# iCEHAX5U1K.net
KiCad netlist of a schematic drawn in EAGLE
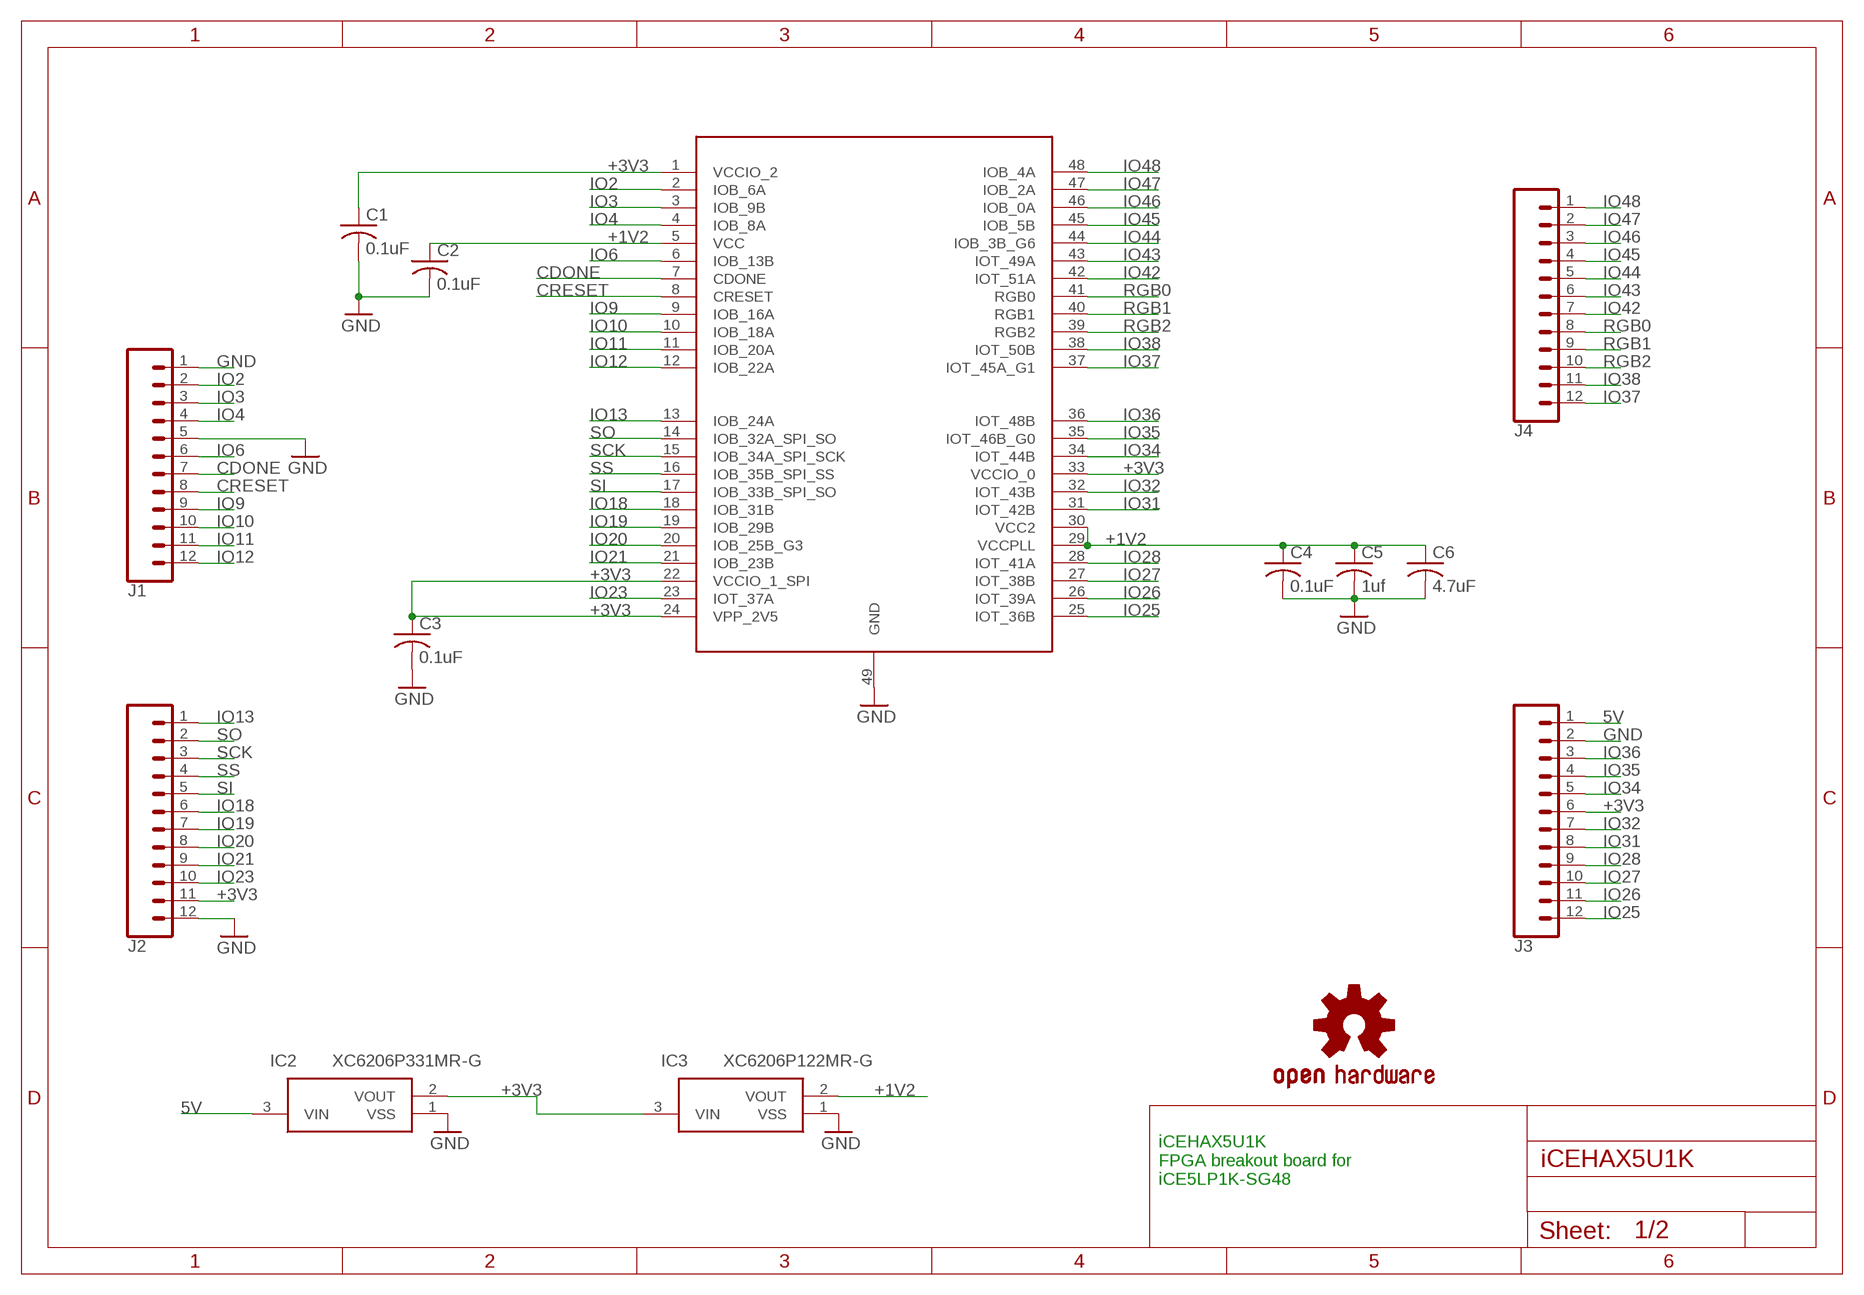
[diagram p0: schematic, sheet 1]
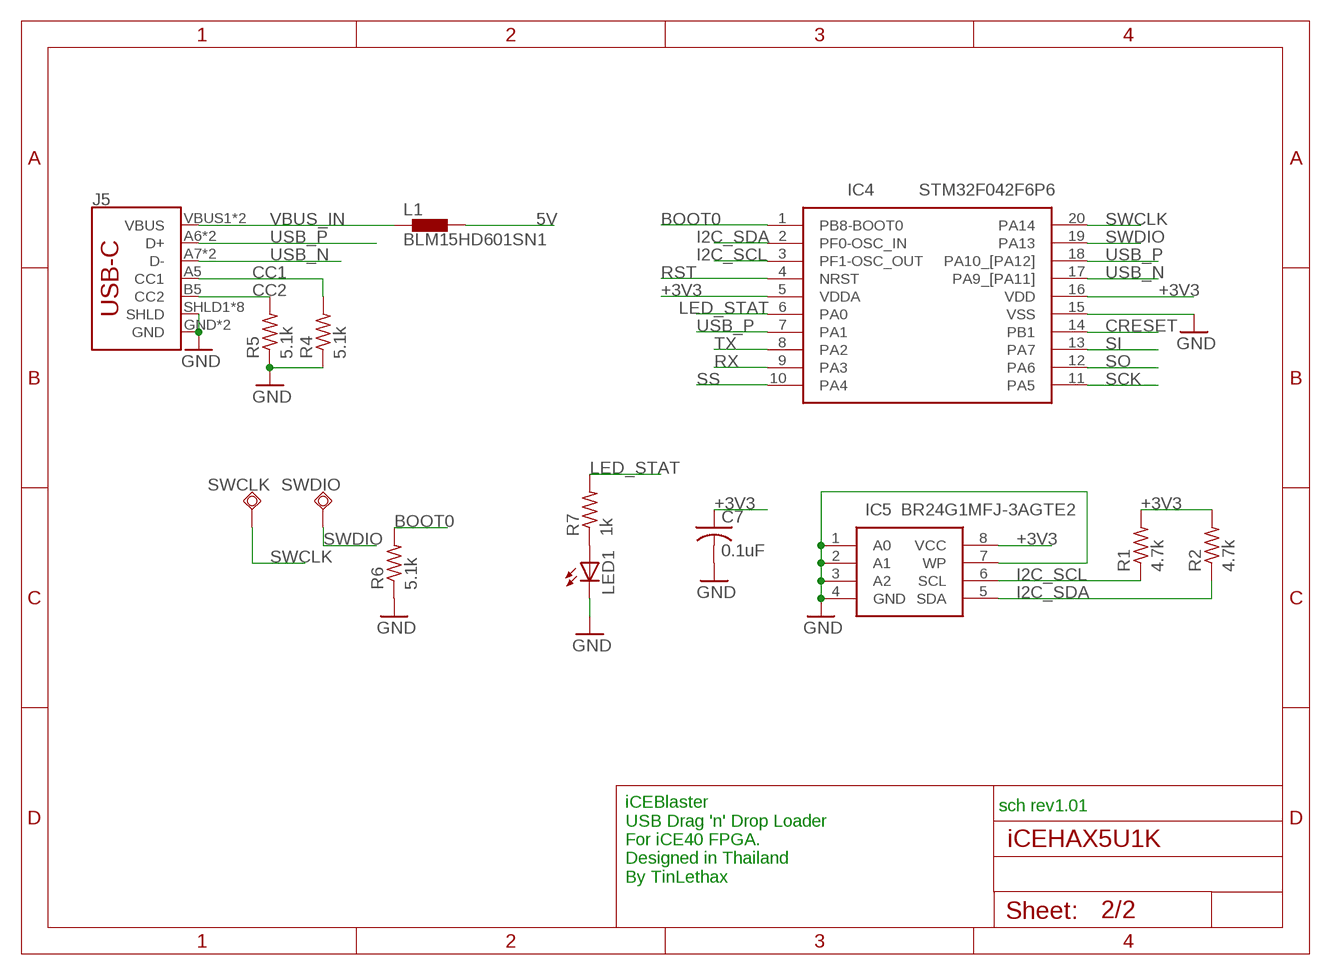
[diagram p1: schematic, sheet 2]

(export (version "E")
  (design (tool "Eeschema 10.0.6"))
  (components
    (comp (ref "C7")
      (value "0.1uF")
      (footprint "eagle-import:C0603")
      (libsource (lib "eagle-import") (part "C-USC0603"))
    )
    (comp (ref "IC4")
      (value "STM32F042F6P6")
      (footprint "eagle-import:SOP65P640X120-20N")
      (fields (field (name "MOUSER_PART_NUMBER") "511-STM32F042F6P6"))
      (libsource (lib "eagle-import") (part "STM32F042F6P6"))
    )
    (comp (ref "IC5")
      (value "BR24G1MFJ-3AGTE2")
      (footprint "eagle-import:SOP126P620X150-8N")
      (libsource (lib "eagle-import") (part "BR24G1MFJ-3AGTE2"))
    )
    (comp (ref "J5")
      (value "SPARKFUN-CONNECTORS_USB_C16PIN")
      (footprint "eagle-import:SPARKFUN-CONNECTORS_USB-C-16P")
      (libsource (lib "eagle-import") (part "SPARKFUN-CONNECTORS_USB_C16PIN"))
    )
    (comp (ref "L1")
      (value "BLM15HD601SN1")
      (footprint "eagle-import:0402")
      (libsource (lib "eagle-import") (part "BLM15HD601SN1"))
    )
    (comp (ref "LED1")
      (value "LEDCHIP-LED0603")
      (footprint "eagle-import:CHIP-LED0603")
      (libsource (lib "eagle-import") (part "LEDCHIP-LED0603"))
    )
    (comp (ref "R1")
      (value "4.7k")
      (footprint "eagle-import:R0603")
      (libsource (lib "eagle-import") (part "R-US_R0603"))
    )
    (comp (ref "R2")
      (value "4.7k")
      (footprint "eagle-import:R0603")
      (libsource (lib "eagle-import") (part "R-US_R0603"))
    )
    (comp (ref "R4")
      (value "5.1k")
      (footprint "eagle-import:R0603")
      (libsource (lib "eagle-import") (part "R-US_R0603"))
    )
    (comp (ref "R5")
      (value "5.1k")
      (footprint "eagle-import:R0603")
      (libsource (lib "eagle-import") (part "R-US_R0603"))
    )
    (comp (ref "R6")
      (value "5.1k")
      (footprint "eagle-import:R0603")
      (libsource (lib "eagle-import") (part "R-US_R0603"))
    )
    (comp (ref "R7")
      (value "1k")
      (footprint "eagle-import:R0603")
      (libsource (lib "eagle-import") (part "R-US_R0603"))
    )
    (comp (ref "SWCLK")
      (value "TPSQTP15SQ")
      (footprint "eagle-import:TP15SQ")
      (libsource (lib "eagle-import") (part "TPSQTP15SQ"))
    )
    (comp (ref "SWDIO")
      (value "TPSQTP15SQ")
      (footprint "eagle-import:TP15SQ")
      (libsource (lib "eagle-import") (part "TPSQTP15SQ"))
    )
    (comp (ref "C1")
      (value "0.1uF")
      (footprint "eagle-import:C0603")
      (libsource (lib "eagle-import") (part "C-USC0603"))
    )
    (comp (ref "C2")
      (value "0.1uF")
      (footprint "eagle-import:C0603")
      (libsource (lib "eagle-import") (part "C-USC0603"))
    )
    (comp (ref "C3")
      (value "0.1uF")
      (footprint "eagle-import:C0603")
      (libsource (lib "eagle-import") (part "C-USC0603"))
    )
    (comp (ref "C4")
      (value "0.1uF")
      (footprint "eagle-import:C0603")
      (libsource (lib "eagle-import") (part "C-USC0603"))
    )
    (comp (ref "C5")
      (value "1uf")
      (footprint "eagle-import:C0603")
      (libsource (lib "eagle-import") (part "C-USC0603"))
    )
    (comp (ref "C6")
      (value "4.7uF")
      (footprint "eagle-import:C0603")
      (libsource (lib "eagle-import") (part "C-USC0603"))
    )
    (comp (ref "IC1")
      (value "ICE5LP1K-SG48")
      (footprint "eagle-import:QFN50P700X700X100-48T535N")
      (libsource (lib "eagle-import") (part "ICE5LP1K-SG48"))
    )
    (comp (ref "IC2")
      (value "XC6206P331MR-G")
      (footprint "eagle-import:SOT95P280X130-3N")
      (fields (field (name "MOUSER_PART_NUMBER") "865-XC6206P331MR-G"))
      (libsource (lib "eagle-import") (part "XC6206P331MR-G"))
    )
    (comp (ref "IC3")
      (value "XC6206P122MR-G")
      (footprint "eagle-import:SOT95P280X130-3N")
      (fields (field (name "MOUSER_PART_NUMBER") "865-XC6206P122MR-G"))
      (libsource (lib "eagle-import") (part "XC6206P122MR-G"))
    )
    (comp (ref "J1")
      (value "CONN_12NO_SILK")
      (footprint "eagle-import:1X12_NO_SILK")
      (libsource (lib "eagle-import") (part "CONN_12NO_SILK"))
    )
    (comp (ref "J2")
      (value "CONN_12NO_SILK")
      (footprint "eagle-import:1X12_NO_SILK")
      (libsource (lib "eagle-import") (part "CONN_12NO_SILK"))
    )
    (comp (ref "J3")
      (value "CONN_12NO_SILK")
      (footprint "eagle-import:1X12_NO_SILK")
      (libsource (lib "eagle-import") (part "CONN_12NO_SILK"))
    )
    (comp (ref "J4")
      (value "CONN_12NO_SILK")
      (footprint "eagle-import:1X12_NO_SILK")
      (libsource (lib "eagle-import") (part "CONN_12NO_SILK"))
    )
    (comp (ref "LOGO1")
      (value "OSHW-LOGOMINI")
      (footprint "eagle-import:OSHW-LOGO-MINI")
      (libsource (lib "eagle-import") (part "OSHW-LOGOMINI"))
    )
  )
  (nets
    (net (code "1") (name "+1V2") (class "Default")
      (node (ref "C2") (pin "1") (pinfunction "1_1") (pintype "passive"))
      (node (ref "C4") (pin "1") (pinfunction "1_1") (pintype "passive"))
      (node (ref "C5") (pin "1") (pinfunction "1_1") (pintype "passive"))
      (node (ref "C6") (pin "1") (pinfunction "1_1") (pintype "passive"))
      (node (ref "IC1") (pin "29") (pinfunction "VCCPLL_29") (pintype "bidirectional"))
      (node (ref "IC1") (pin "30") (pinfunction "VCC2_30") (pintype "bidirectional"))
      (node (ref "IC1") (pin "5") (pinfunction "VCC_5") (pintype "bidirectional"))
      (node (ref "IC3") (pin "2") (pinfunction "VOUT_2") (pintype "bidirectional"))
    )
    (net (code "2") (name "+3V3") (class "Default")
      (node (ref "C1") (pin "1") (pinfunction "1_1") (pintype "passive"))
      (node (ref "C3") (pin "1") (pinfunction "1_1") (pintype "passive"))
      (node (ref "C7") (pin "1") (pinfunction "1_1") (pintype "passive"))
      (node (ref "IC1") (pin "1") (pinfunction "VCCIO_2_1") (pintype "bidirectional"))
      (node (ref "IC1") (pin "22") (pinfunction "VCCIO_1_SPI_22") (pintype "bidirectional"))
      (node (ref "IC1") (pin "24") (pinfunction "VPP_2V5_24") (pintype "bidirectional"))
      (node (ref "IC1") (pin "33") (pinfunction "VCCIO_0_33") (pintype "bidirectional"))
      (node (ref "IC2") (pin "2") (pinfunction "VOUT_2") (pintype "output"))
      (node (ref "IC3") (pin "3") (pinfunction "VIN_3") (pintype "bidirectional"))
      (node (ref "IC4") (pin "16") (pinfunction "VDD_16") (pintype "bidirectional"))
      (node (ref "IC4") (pin "5") (pinfunction "VDDA_5") (pintype "bidirectional"))
      (node (ref "IC5") (pin "8") (pinfunction "VCC_8") (pintype "power_in"))
      (node (ref "J2") (pin "11") (pinfunction "11_11") (pintype "passive"))
      (node (ref "J3") (pin "6") (pinfunction "6_6") (pintype "passive"))
      (node (ref "R1") (pin "2") (pinfunction "2_2") (pintype "passive"))
      (node (ref "R2") (pin "2") (pinfunction "2_2") (pintype "passive"))
    )
    (net (code "3") (name "5V") (class "Default")
      (node (ref "IC2") (pin "3") (pinfunction "VIN_3") (pintype "bidirectional"))
      (node (ref "J3") (pin "1") (pinfunction "1_1") (pintype "passive"))
      (node (ref "L1") (pin "2") (pinfunction "2_2") (pintype "passive"))
    )
    (net (code "4") (name "BOOT0") (class "Default")
      (node (ref "IC4") (pin "1") (pinfunction "PB8-BOOT0_1") (pintype "bidirectional"))
      (node (ref "R6") (pin "2") (pinfunction "2_2") (pintype "passive"))
    )
    (net (code "5") (name "CC1") (class "Default")
      (node (ref "J5") (pin "A5") (pinfunction "CC1_A5") (pintype "bidirectional"))
      (node (ref "R4") (pin "2") (pinfunction "2_2") (pintype "passive"))
    )
    (net (code "6") (name "CC2") (class "Default")
      (node (ref "J5") (pin "B5") (pinfunction "CC2_B5") (pintype "bidirectional"))
      (node (ref "R5") (pin "2") (pinfunction "2_2") (pintype "passive"))
    )
    (net (code "7") (name "CDONE") (class "Default")
      (node (ref "IC1") (pin "7") (pinfunction "CDONE_7") (pintype "bidirectional"))
      (node (ref "J1") (pin "7") (pinfunction "7_7") (pintype "passive"))
    )
    (net (code "8") (name "CRESET") (class "Default")
      (node (ref "IC1") (pin "8") (pinfunction "CRESET_8") (pintype "bidirectional"))
      (node (ref "IC4") (pin "14") (pinfunction "PB1_14") (pintype "bidirectional"))
      (node (ref "J1") (pin "8") (pinfunction "8_8") (pintype "passive"))
    )
    (net (code "9") (name "GND") (class "Default")
      (node (ref "C1") (pin "2") (pinfunction "2_2") (pintype "passive"))
      (node (ref "C2") (pin "2") (pinfunction "2_2") (pintype "passive"))
      (node (ref "C3") (pin "2") (pinfunction "2_2") (pintype "passive"))
      (node (ref "C4") (pin "2") (pinfunction "2_2") (pintype "passive"))
      (node (ref "C5") (pin "2") (pinfunction "2_2") (pintype "passive"))
      (node (ref "C6") (pin "2") (pinfunction "2_2") (pintype "passive"))
      (node (ref "C7") (pin "2") (pinfunction "2_2") (pintype "passive"))
      (node (ref "IC1") (pin "49") (pinfunction "GND_49") (pintype "bidirectional"))
      (node (ref "IC2") (pin "1") (pinfunction "VSS_1") (pintype "power_in"))
      (node (ref "IC3") (pin "1") (pinfunction "VSS_1") (pintype "bidirectional"))
      (node (ref "IC4") (pin "15") (pinfunction "VSS_15") (pintype "bidirectional"))
      (node (ref "IC5") (pin "1") (pinfunction "A0_1") (pintype "input"))
      (node (ref "IC5") (pin "2") (pinfunction "A1_2") (pintype "input"))
      (node (ref "IC5") (pin "3") (pinfunction "A2_3") (pintype "bidirectional"))
      (node (ref "IC5") (pin "4") (pinfunction "GND_4") (pintype "power_in"))
      (node (ref "IC5") (pin "7") (pinfunction "WP_7") (pintype "input"))
      (node (ref "J1") (pin "1") (pinfunction "1_1") (pintype "passive"))
      (node (ref "J1") (pin "5") (pinfunction "5_5") (pintype "passive"))
      (node (ref "J2") (pin "12") (pinfunction "12_12") (pintype "passive"))
      (node (ref "J3") (pin "2") (pinfunction "2_2") (pintype "passive"))
      (node (ref "J5") (pin "GND") (pinfunction "GND_GND") (pintype "bidirectional"))
      (node (ref "J5") (pin "GND2") (pinfunction "GND_GND2") (pintype "bidirectional"))
      (node (ref "J5") (pin "SHLD1") (pinfunction "SHLD_SHLD1") (pintype "bidirectional"))
      (node (ref "J5") (pin "SHLD2") (pinfunction "SHLD_SHLD2") (pintype "bidirectional"))
      (node (ref "J5") (pin "SHLD3") (pinfunction "SHLD_SHLD3") (pintype "bidirectional"))
      (node (ref "J5") (pin "SHLD4") (pinfunction "SHLD_SHLD4") (pintype "bidirectional"))
      (node (ref "J5") (pin "SHLD5") (pinfunction "SHLD_SHLD5") (pintype "bidirectional"))
      (node (ref "J5") (pin "SHLD6") (pinfunction "SHLD_SHLD6") (pintype "bidirectional"))
      (node (ref "J5") (pin "SHLD7") (pinfunction "SHLD_SHLD7") (pintype "bidirectional"))
      (node (ref "J5") (pin "SHLD8") (pinfunction "SHLD_SHLD8") (pintype "bidirectional"))
      (node (ref "LED1") (pin "C") (pinfunction "C_C") (pintype "passive"))
      (node (ref "R4") (pin "1") (pinfunction "1_1") (pintype "passive"))
      (node (ref "R5") (pin "1") (pinfunction "1_1") (pintype "passive"))
      (node (ref "R6") (pin "1") (pinfunction "1_1") (pintype "passive"))
    )
    (net (code "10") (name "I2C_SCL") (class "Default")
      (node (ref "IC4") (pin "3") (pinfunction "PF1-OSC_OUT_3") (pintype "bidirectional"))
      (node (ref "IC5") (pin "6") (pinfunction "SCL_6") (pintype "input"))
      (node (ref "R1") (pin "1") (pinfunction "1_1") (pintype "passive"))
    )
    (net (code "11") (name "I2C_SDA") (class "Default")
      (node (ref "IC4") (pin "2") (pinfunction "PF0-OSC_IN_2") (pintype "bidirectional"))
      (node (ref "IC5") (pin "5") (pinfunction "SDA_5") (pintype "bidirectional"))
      (node (ref "R2") (pin "1") (pinfunction "1_1") (pintype "passive"))
    )
    (net (code "12") (name "IO2") (class "Default")
      (node (ref "IC1") (pin "2") (pinfunction "IOB_6A_2") (pintype "bidirectional"))
      (node (ref "J1") (pin "2") (pinfunction "2_2") (pintype "passive"))
    )
    (net (code "13") (name "IO3") (class "Default")
      (node (ref "IC1") (pin "3") (pinfunction "IOB_9B_3") (pintype "bidirectional"))
      (node (ref "J1") (pin "3") (pinfunction "3_3") (pintype "passive"))
    )
    (net (code "14") (name "IO4") (class "Default")
      (node (ref "IC1") (pin "4") (pinfunction "IOB_8A_4") (pintype "bidirectional"))
      (node (ref "J1") (pin "4") (pinfunction "4_4") (pintype "passive"))
    )
    (net (code "15") (name "IO6") (class "Default")
      (node (ref "IC1") (pin "6") (pinfunction "IOB_13B_6") (pintype "bidirectional"))
      (node (ref "J1") (pin "6") (pinfunction "6_6") (pintype "passive"))
    )
    (net (code "16") (name "IO9") (class "Default")
      (node (ref "IC1") (pin "9") (pinfunction "IOB_16A_9") (pintype "bidirectional"))
      (node (ref "J1") (pin "9") (pinfunction "9_9") (pintype "passive"))
    )
    (net (code "17") (name "IO10") (class "Default")
      (node (ref "IC1") (pin "10") (pinfunction "IOB_18A_10") (pintype "bidirectional"))
      (node (ref "J1") (pin "10") (pinfunction "10_10") (pintype "passive"))
    )
    (net (code "18") (name "IO11") (class "Default")
      (node (ref "IC1") (pin "11") (pinfunction "IOB_20A_11") (pintype "bidirectional"))
      (node (ref "J1") (pin "11") (pinfunction "11_11") (pintype "passive"))
    )
    (net (code "19") (name "IO12") (class "Default")
      (node (ref "IC1") (pin "12") (pinfunction "IOB_22A_12") (pintype "bidirectional"))
      (node (ref "J1") (pin "12") (pinfunction "12_12") (pintype "passive"))
    )
    (net (code "20") (name "IO13") (class "Default")
      (node (ref "IC1") (pin "13") (pinfunction "IOB_24A_13") (pintype "bidirectional"))
      (node (ref "J2") (pin "1") (pinfunction "1_1") (pintype "passive"))
    )
    (net (code "21") (name "IO18") (class "Default")
      (node (ref "IC1") (pin "18") (pinfunction "IOB_31B_18") (pintype "bidirectional"))
      (node (ref "J2") (pin "6") (pinfunction "6_6") (pintype "passive"))
    )
    (net (code "22") (name "IO19") (class "Default")
      (node (ref "IC1") (pin "19") (pinfunction "IOB_29B_19") (pintype "bidirectional"))
      (node (ref "J2") (pin "7") (pinfunction "7_7") (pintype "passive"))
    )
    (net (code "23") (name "IO20") (class "Default")
      (node (ref "IC1") (pin "20") (pinfunction "IOB_25B_G3_20") (pintype "bidirectional"))
      (node (ref "J2") (pin "8") (pinfunction "8_8") (pintype "passive"))
    )
    (net (code "24") (name "IO21") (class "Default")
      (node (ref "IC1") (pin "21") (pinfunction "IOB_23B_21") (pintype "bidirectional"))
      (node (ref "J2") (pin "9") (pinfunction "9_9") (pintype "passive"))
    )
    (net (code "25") (name "IO23") (class "Default")
      (node (ref "IC1") (pin "23") (pinfunction "IOT_37A_23") (pintype "bidirectional"))
      (node (ref "J2") (pin "10") (pinfunction "10_10") (pintype "passive"))
    )
    (net (code "26") (name "IO25") (class "Default")
      (node (ref "IC1") (pin "25") (pinfunction "IOT_36B_25") (pintype "bidirectional"))
      (node (ref "J3") (pin "12") (pinfunction "12_12") (pintype "passive"))
    )
    (net (code "27") (name "IO26") (class "Default")
      (node (ref "IC1") (pin "26") (pinfunction "IOT_39A_26") (pintype "bidirectional"))
      (node (ref "J3") (pin "11") (pinfunction "11_11") (pintype "passive"))
    )
    (net (code "28") (name "IO27") (class "Default")
      (node (ref "IC1") (pin "27") (pinfunction "IOT_38B_27") (pintype "bidirectional"))
      (node (ref "J3") (pin "10") (pinfunction "10_10") (pintype "passive"))
    )
    (net (code "29") (name "IO28") (class "Default")
      (node (ref "IC1") (pin "28") (pinfunction "IOT_41A_28") (pintype "bidirectional"))
      (node (ref "J3") (pin "9") (pinfunction "9_9") (pintype "passive"))
    )
    (net (code "30") (name "IO31") (class "Default")
      (node (ref "IC1") (pin "31") (pinfunction "IOT_42B_31") (pintype "bidirectional"))
      (node (ref "J3") (pin "8") (pinfunction "8_8") (pintype "passive"))
    )
    (net (code "31") (name "IO32") (class "Default")
      (node (ref "IC1") (pin "32") (pinfunction "IOT_43B_32") (pintype "bidirectional"))
      (node (ref "J3") (pin "7") (pinfunction "7_7") (pintype "passive"))
    )
    (net (code "32") (name "IO34") (class "Default")
      (node (ref "IC1") (pin "34") (pinfunction "IOT_44B_34") (pintype "bidirectional"))
      (node (ref "J3") (pin "5") (pinfunction "5_5") (pintype "passive"))
    )
    (net (code "33") (name "IO35") (class "Default")
      (node (ref "IC1") (pin "35") (pinfunction "IOT_46B_G0_35") (pintype "bidirectional"))
      (node (ref "J3") (pin "4") (pinfunction "4_4") (pintype "passive"))
    )
    (net (code "34") (name "IO36") (class "Default")
      (node (ref "IC1") (pin "36") (pinfunction "IOT_48B_36") (pintype "bidirectional"))
      (node (ref "J3") (pin "3") (pinfunction "3_3") (pintype "passive"))
    )
    (net (code "35") (name "IO37") (class "Default")
      (node (ref "IC1") (pin "37") (pinfunction "IOT_45A_G1_37") (pintype "bidirectional"))
      (node (ref "J4") (pin "12") (pinfunction "12_12") (pintype "passive"))
    )
    (net (code "36") (name "IO38") (class "Default")
      (node (ref "IC1") (pin "38") (pinfunction "IOT_50B_38") (pintype "bidirectional"))
      (node (ref "J4") (pin "11") (pinfunction "11_11") (pintype "passive"))
    )
    (net (code "37") (name "IO42") (class "Default")
      (node (ref "IC1") (pin "42") (pinfunction "IOT_51A_42") (pintype "bidirectional"))
      (node (ref "J4") (pin "7") (pinfunction "7_7") (pintype "passive"))
    )
    (net (code "38") (name "IO43") (class "Default")
      (node (ref "IC1") (pin "43") (pinfunction "IOT_49A_43") (pintype "bidirectional"))
      (node (ref "J4") (pin "6") (pinfunction "6_6") (pintype "passive"))
    )
    (net (code "39") (name "IO44") (class "Default")
      (node (ref "IC1") (pin "44") (pinfunction "IOB_3B_G6_44") (pintype "bidirectional"))
      (node (ref "J4") (pin "5") (pinfunction "5_5") (pintype "passive"))
    )
    (net (code "40") (name "IO45") (class "Default")
      (node (ref "IC1") (pin "45") (pinfunction "IOB_5B_45") (pintype "bidirectional"))
      (node (ref "J4") (pin "4") (pinfunction "4_4") (pintype "passive"))
    )
    (net (code "41") (name "IO46") (class "Default")
      (node (ref "IC1") (pin "46") (pinfunction "IOB_0A_46") (pintype "bidirectional"))
      (node (ref "J4") (pin "3") (pinfunction "3_3") (pintype "passive"))
    )
    (net (code "42") (name "IO47") (class "Default")
      (node (ref "IC1") (pin "47") (pinfunction "IOB_2A_47") (pintype "bidirectional"))
      (node (ref "J4") (pin "2") (pinfunction "2_2") (pintype "passive"))
    )
    (net (code "43") (name "IO48") (class "Default")
      (node (ref "IC1") (pin "48") (pinfunction "IOB_4A_48") (pintype "bidirectional"))
      (node (ref "J4") (pin "1") (pinfunction "1_1") (pintype "passive"))
    )
    (net (code "44") (name "LED_STAT") (class "Default")
      (node (ref "IC4") (pin "6") (pinfunction "PA0_6") (pintype "bidirectional"))
      (node (ref "R7") (pin "2") (pinfunction "2_2") (pintype "passive"))
    )
    (net (code "45") (name "Net-(LED1-PadA)") (class "Default")
      (node (ref "LED1") (pin "A") (pinfunction "A_A") (pintype "passive"))
      (node (ref "R7") (pin "1") (pinfunction "1_1") (pintype "passive"))
    )
    (net (code "46") (name "RGB0") (class "Default")
      (node (ref "IC1") (pin "41") (pinfunction "RGB0_41") (pintype "bidirectional"))
      (node (ref "J4") (pin "8") (pinfunction "8_8") (pintype "passive"))
    )
    (net (code "47") (name "RGB1") (class "Default")
      (node (ref "IC1") (pin "40") (pinfunction "RGB1_40") (pintype "bidirectional"))
      (node (ref "J4") (pin "9") (pinfunction "9_9") (pintype "passive"))
    )
    (net (code "48") (name "RGB2") (class "Default")
      (node (ref "IC1") (pin "39") (pinfunction "RGB2_39") (pintype "bidirectional"))
      (node (ref "J4") (pin "10") (pinfunction "10_10") (pintype "passive"))
    )
    (net (code "49") (name "RST") (class "Default")
      (node (ref "IC4") (pin "4") (pinfunction "NRST_4") (pintype "bidirectional"))
    )
    (net (code "50") (name "RX") (class "Default")
      (node (ref "IC4") (pin "9") (pinfunction "PA3_9") (pintype "bidirectional"))
    )
    (net (code "51") (name "SCK") (class "Default")
      (node (ref "IC1") (pin "15") (pinfunction "IOB_34A_SPI_SCK_15") (pintype "bidirectional"))
      (node (ref "IC4") (pin "11") (pinfunction "PA5_11") (pintype "bidirectional"))
      (node (ref "J2") (pin "3") (pinfunction "3_3") (pintype "passive"))
    )
    (net (code "52") (name "SI") (class "Default")
      (node (ref "IC1") (pin "17") (pinfunction "IOB_33B_SPI_SO_17") (pintype "bidirectional"))
      (node (ref "IC4") (pin "13") (pinfunction "PA7_13") (pintype "bidirectional"))
      (node (ref "J2") (pin "5") (pinfunction "5_5") (pintype "passive"))
    )
    (net (code "53") (name "SO") (class "Default")
      (node (ref "IC1") (pin "14") (pinfunction "IOB_32A_SPI_SO_14") (pintype "bidirectional"))
      (node (ref "IC4") (pin "12") (pinfunction "PA6_12") (pintype "bidirectional"))
      (node (ref "J2") (pin "2") (pinfunction "2_2") (pintype "passive"))
    )
    (net (code "54") (name "SS") (class "Default")
      (node (ref "IC1") (pin "16") (pinfunction "IOB_35B_SPI_SS_16") (pintype "bidirectional"))
      (node (ref "IC4") (pin "10") (pinfunction "PA4_10") (pintype "bidirectional"))
      (node (ref "J2") (pin "4") (pinfunction "4_4") (pintype "passive"))
    )
    (net (code "55") (name "SWCLK") (class "Default")
      (node (ref "IC4") (pin "20") (pinfunction "PA14_20") (pintype "bidirectional"))
      (node (ref "SWCLK") (pin "TP") (pinfunction "TP_TP") (pintype "input"))
    )
    (net (code "56") (name "SWDIO") (class "Default")
      (node (ref "IC4") (pin "19") (pinfunction "PA13_19") (pintype "bidirectional"))
      (node (ref "SWDIO") (pin "TP") (pinfunction "TP_TP") (pintype "input"))
    )
    (net (code "57") (name "TX") (class "Default")
      (node (ref "IC4") (pin "8") (pinfunction "PA2_8") (pintype "bidirectional"))
    )
    (net (code "58") (name "USB_N") (class "Default")
      (node (ref "IC4") (pin "17") (pinfunction "PA9_[PA11]_17") (pintype "bidirectional"))
      (node (ref "J5") (pin "A7") (pinfunction "D-_A7") (pintype "bidirectional"))
      (node (ref "J5") (pin "B7") (pinfunction "D-_B7") (pintype "bidirectional"))
    )
    (net (code "59") (name "USB_P") (class "Default")
      (node (ref "IC4") (pin "18") (pinfunction "PA10_[PA12]_18") (pintype "bidirectional"))
      (node (ref "IC4") (pin "7") (pinfunction "PA1_7") (pintype "bidirectional"))
      (node (ref "J5") (pin "A6") (pinfunction "D+_A6") (pintype "bidirectional"))
      (node (ref "J5") (pin "B6") (pinfunction "D+_B6") (pintype "bidirectional"))
    )
    (net (code "60") (name "VBUS_IN") (class "Default")
      (node (ref "J5") (pin "VBUS1") (pinfunction "VBUS_VBUS1") (pintype "bidirectional"))
      (node (ref "J5") (pin "VBUS2") (pinfunction "VBUS_VBUS2") (pintype "bidirectional"))
      (node (ref "L1") (pin "1") (pinfunction "1_1") (pintype "passive"))
    )
  )
)
